# source.net
KiCad netlist of a schematic drawn in Altium Designer
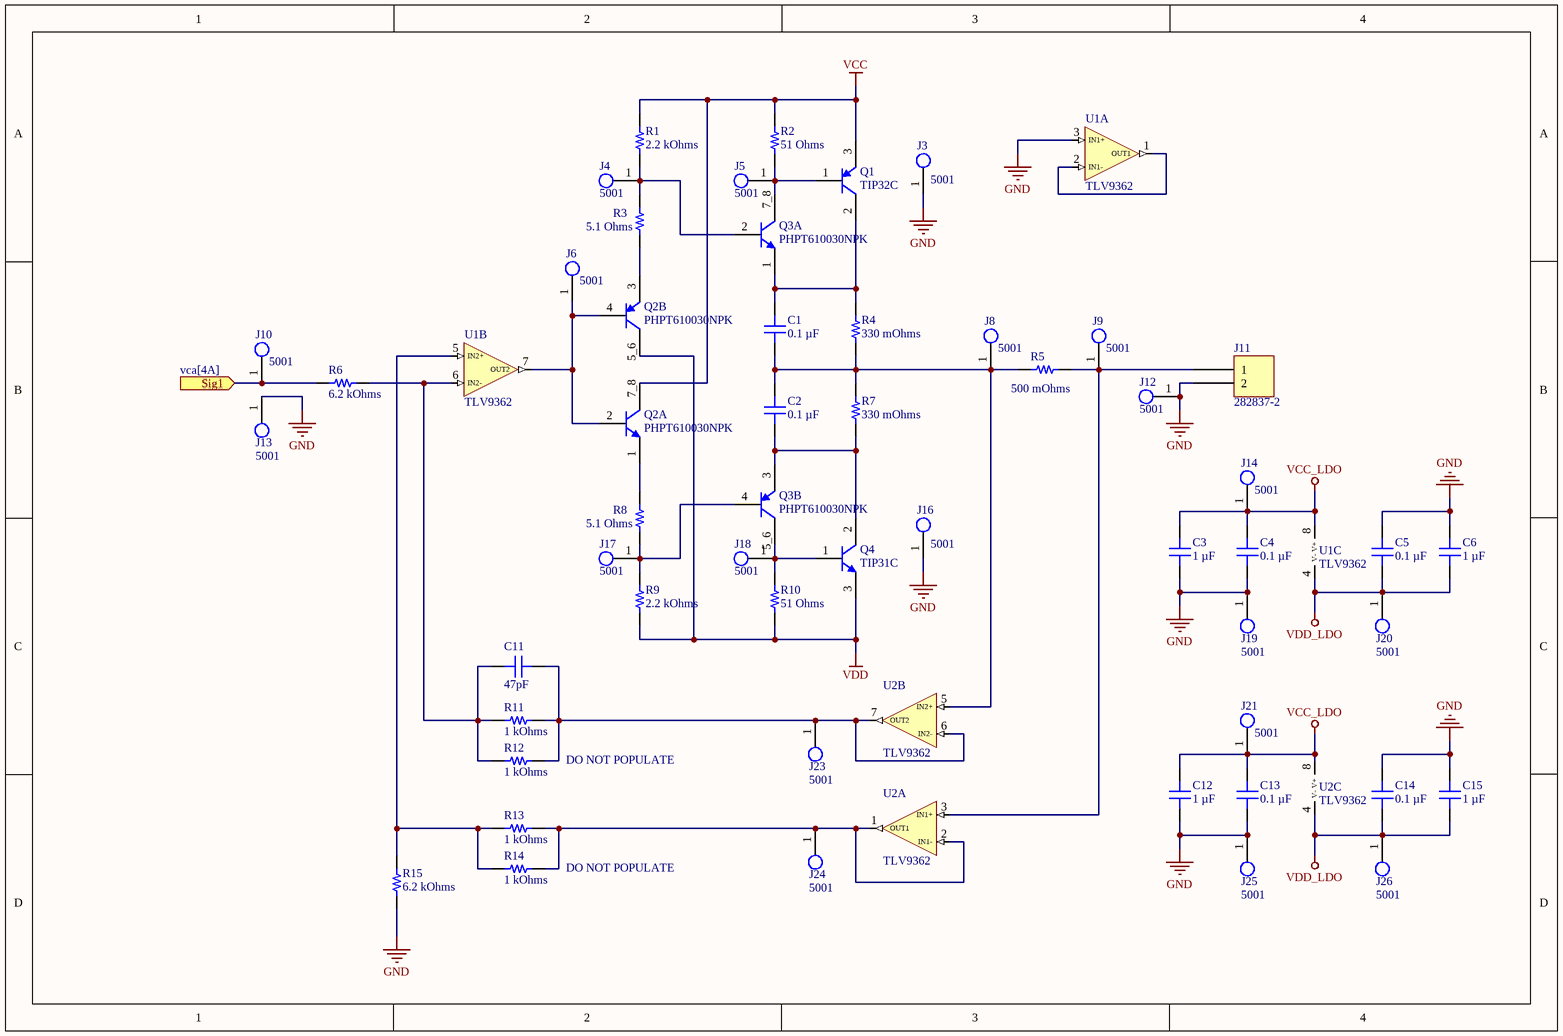
[diagram p0: source.SchDoc]

(export (version "E")
  (design (tool "Eeschema 10.0.6"))
  (components
    (comp (ref "C1")
      (value "0.1 µF")
      (footprint "CAP 1206_3216 - 0.8MM")
      (description "CAP CER 0.1UF 50V X7R 1206")
      (fields
        (field (name "PART NUMBER") "885012208087")
        (field (name "CAPACITANCE") "0.1 µF")
        (field (name "MANUFACTURER") "Würth Elektronik")
      )
      (libsource (lib "Celestial Altium Library - altium_library") (part "Capacitor"))
    )
    (comp (ref "C2")
      (value "0.1 µF")
      (footprint "CAP 1206_3216 - 0.8MM")
      (description "CAP CER 0.1UF 50V X7R 1206")
      (fields
        (field (name "PART NUMBER") "885012208087")
        (field (name "CAPACITANCE") "0.1 µF")
        (field (name "MANUFACTURER") "Würth Elektronik")
      )
      (libsource (lib "Celestial Altium Library - altium_library") (part "Capacitor"))
    )
    (comp (ref "C3")
      (value "1 µF")
      (footprint "CAP 1206_3216 - 0.8MM")
      (description "CAP CER 1UF 50V X7R 1206")
      (fields
        (field (name "PART NUMBER") "885012208093")
        (field (name "CAPACITANCE") "1 µF")
        (field (name "MANUFACTURER") "Würth Elektronik")
      )
      (libsource (lib "Celestial Altium Library - altium_library") (part "Capacitor"))
    )
    (comp (ref "C4")
      (value "0.1 µF")
      (footprint "CAP 1206_3216 - 0.8MM")
      (description "CAP CER 0.1UF 50V X7R 1206")
      (fields
        (field (name "PART NUMBER") "885012208087")
        (field (name "CAPACITANCE") "0.1 µF")
        (field (name "MANUFACTURER") "Würth Elektronik")
      )
      (libsource (lib "Celestial Altium Library - altium_library") (part "Capacitor"))
    )
    (comp (ref "C5")
      (value "0.1 µF")
      (footprint "CAP 1206_3216 - 0.8MM")
      (description "CAP CER 0.1UF 50V X7R 1206")
      (fields
        (field (name "PART NUMBER") "885012208087")
        (field (name "CAPACITANCE") "0.1 µF")
        (field (name "MANUFACTURER") "Würth Elektronik")
      )
      (libsource (lib "Celestial Altium Library - altium_library") (part "Capacitor"))
    )
    (comp (ref "C6")
      (value "1 µF")
      (footprint "CAP 1206_3216 - 0.8MM")
      (description "CAP CER 1UF 50V X7R 1206")
      (fields
        (field (name "PART NUMBER") "885012208093")
        (field (name "CAPACITANCE") "1 µF")
        (field (name "MANUFACTURER") "Würth Elektronik")
      )
      (libsource (lib "Celestial Altium Library - altium_library") (part "Capacitor"))
    )
    (comp (ref "C11")
      (value "47pF")
      (footprint "CAP 1206_3216 - 1.8MM")
      (description "CAP CER 47PF 1KV C0G/NP0 1206")
      (fields
        (field (name "PART NUMBER") "1206AA470KAT1A")
        (field (name "CAPACITANCE") "47pF")
        (field (name "MANUFACTURER") "AVX Corporation")
      )
      (libsource (lib "Celestial Altium Library - altium_library") (part "Capacitor"))
    )
    (comp (ref "C12")
      (value "1 µF")
      (footprint "CAP 1206_3216 - 0.8MM")
      (description "CAP CER 1UF 50V X7R 1206")
      (fields
        (field (name "PART NUMBER") "885012208093")
        (field (name "CAPACITANCE") "1 µF")
        (field (name "MANUFACTURER") "Würth Elektronik")
      )
      (libsource (lib "Celestial Altium Library - altium_library") (part "Capacitor"))
    )
    (comp (ref "C13")
      (value "0.1 µF")
      (footprint "CAP 1206_3216 - 0.8MM")
      (description "CAP CER 0.1UF 50V X7R 1206")
      (fields
        (field (name "PART NUMBER") "885012208087")
        (field (name "CAPACITANCE") "0.1 µF")
        (field (name "MANUFACTURER") "Würth Elektronik")
      )
      (libsource (lib "Celestial Altium Library - altium_library") (part "Capacitor"))
    )
    (comp (ref "C14")
      (value "0.1 µF")
      (footprint "CAP 1206_3216 - 0.8MM")
      (description "CAP CER 0.1UF 50V X7R 1206")
      (fields
        (field (name "PART NUMBER") "885012208087")
        (field (name "CAPACITANCE") "0.1 µF")
        (field (name "MANUFACTURER") "Würth Elektronik")
      )
      (libsource (lib "Celestial Altium Library - altium_library") (part "Capacitor"))
    )
    (comp (ref "C15")
      (value "1 µF")
      (footprint "CAP 1206_3216 - 0.8MM")
      (description "CAP CER 1UF 50V X7R 1206")
      (fields
        (field (name "PART NUMBER") "885012208093")
        (field (name "CAPACITANCE") "1 µF")
        (field (name "MANUFACTURER") "Würth Elektronik")
      )
      (libsource (lib "Celestial Altium Library - altium_library") (part "Capacitor"))
    )
    (comp (ref "J3")
      (value "5001")
      (footprint "FP-5001-MFG")
      (description "PC TEST POINT MINIATURE BLACK")
      (libsource (lib "za_koncar") (part "CMP-2000-05181-2"))
    )
    (comp (ref "J4")
      (value "5001")
      (footprint "FP-5001-MFG")
      (description "PC TEST POINT MINIATURE BLACK")
      (libsource (lib "za_koncar") (part "CMP-2000-05181-2"))
    )
    (comp (ref "J5")
      (value "5001")
      (footprint "FP-5001-MFG")
      (description "PC TEST POINT MINIATURE BLACK")
      (libsource (lib "za_koncar") (part "CMP-2000-05181-2"))
    )
    (comp (ref "J6")
      (value "5001")
      (footprint "FP-5001-MFG")
      (description "PC TEST POINT MINIATURE BLACK")
      (libsource (lib "za_koncar") (part "CMP-2000-05181-2"))
    )
    (comp (ref "J8")
      (value "5001")
      (footprint "FP-5001-MFG")
      (description "PC TEST POINT MINIATURE BLACK")
      (libsource (lib "za_koncar") (part "CMP-2000-05181-2"))
    )
    (comp (ref "J9")
      (value "5001")
      (footprint "FP-5001-MFG")
      (description "PC TEST POINT MINIATURE BLACK")
      (libsource (lib "za_koncar") (part "CMP-2000-05181-2"))
    )
    (comp (ref "J10")
      (value "5001")
      (footprint "FP-5001-MFG")
      (description "PC TEST POINT MINIATURE BLACK")
      (libsource (lib "za_koncar") (part "CMP-2000-05181-2"))
    )
    (comp (ref "J11")
      (value "282837-2")
      (footprint "TE 282837-2")
      (description "TERM BLK 2P SIDE ENT 5.08MM PCB")
      (fields (field (name "MANUFACTURER") "TE Connectivity AMP Connectors") (field (name "VOLTAGE") "300 V"))
      (libsource (lib "Celestial Altium Library - altium_library") (part "2 Pin"))
    )
    (comp (ref "J12")
      (value "5001")
      (footprint "FP-5001-MFG")
      (description "PC TEST POINT MINIATURE BLACK")
      (libsource (lib "za_koncar") (part "CMP-2000-05181-2"))
    )
    (comp (ref "J13")
      (value "5001")
      (footprint "FP-5001-MFG")
      (description "PC TEST POINT MINIATURE BLACK")
      (libsource (lib "za_koncar") (part "CMP-2000-05181-2"))
    )
    (comp (ref "J14")
      (value "5001")
      (footprint "FP-5001-MFG")
      (description "PC TEST POINT MINIATURE BLACK")
      (libsource (lib "za_koncar") (part "CMP-2000-05181-2"))
    )
    (comp (ref "J16")
      (value "5001")
      (footprint "FP-5001-MFG")
      (description "PC TEST POINT MINIATURE BLACK")
      (libsource (lib "za_koncar") (part "CMP-2000-05181-2"))
    )
    (comp (ref "J17")
      (value "5001")
      (footprint "FP-5001-MFG")
      (description "PC TEST POINT MINIATURE BLACK")
      (libsource (lib "za_koncar") (part "CMP-2000-05181-2"))
    )
    (comp (ref "J18")
      (value "5001")
      (footprint "FP-5001-MFG")
      (description "PC TEST POINT MINIATURE BLACK")
      (libsource (lib "za_koncar") (part "CMP-2000-05181-2"))
    )
    (comp (ref "J19")
      (value "5001")
      (footprint "FP-5001-MFG")
      (description "PC TEST POINT MINIATURE BLACK")
      (libsource (lib "za_koncar") (part "CMP-2000-05181-2"))
    )
    (comp (ref "J20")
      (value "5001")
      (footprint "FP-5001-MFG")
      (description "PC TEST POINT MINIATURE BLACK")
      (libsource (lib "za_koncar") (part "CMP-2000-05181-2"))
    )
    (comp (ref "J21")
      (value "5001")
      (footprint "FP-5001-MFG")
      (description "PC TEST POINT MINIATURE BLACK")
      (libsource (lib "za_koncar") (part "CMP-2000-05181-2"))
    )
    (comp (ref "J23")
      (value "5001")
      (footprint "FP-5001-MFG")
      (description "PC TEST POINT MINIATURE BLACK")
      (libsource (lib "za_koncar") (part "CMP-2000-05181-2"))
    )
    (comp (ref "J24")
      (value "5001")
      (footprint "FP-5001-MFG")
      (description "PC TEST POINT MINIATURE BLACK")
      (libsource (lib "za_koncar") (part "CMP-2000-05181-2"))
    )
    (comp (ref "J25")
      (value "5001")
      (footprint "FP-5001-MFG")
      (description "PC TEST POINT MINIATURE BLACK")
      (libsource (lib "za_koncar") (part "CMP-2000-05181-2"))
    )
    (comp (ref "J26")
      (value "5001")
      (footprint "FP-5001-MFG")
      (description "PC TEST POINT MINIATURE BLACK")
      (libsource (lib "za_koncar") (part "CMP-2000-05181-2"))
    )
    (comp (ref "Q1")
      (value "TIP32C")
      (footprint "ONSC-TO-220-3-221A-09")
      (description "Complementary Silicon Plastic Power Transistor, 3-Pin TO-220, Tube")
      (fields (field (name "MANUFACTURER") "On Semiconductor"))
      (libsource (lib "ON Semi General Purpose Transistors") (part "TIP32C"))
    )
    (comp (ref "Q2")
      (value "PHPT610030NPK")
      (footprint "TRANS_BUK9K18-40E,115")
      (libsource (lib "za_koncar") (part "PHPT610030NPK"))
    )
    (comp (ref "Q3")
      (value "PHPT610030NPK")
      (footprint "TRANS_BUK9K18-40E,115")
      (libsource (lib "za_koncar") (part "PHPT610030NPK"))
    )
    (comp (ref "Q4")
      (value "TIP31C")
      (footprint "ONSC-TO-220-3-221A-09")
      (description "Complementary Silicon Plastic Power Transistor, 3-Pin TO-220, Tube")
      (fields (field (name "MANUFACTURER") "On Semiconductor"))
      (libsource (lib "ON Semi General Purpose Transistors") (part "TIP31C"))
    )
    (comp (ref "R1")
      (value "2.2 kOhms")
      (footprint "RES 1206_3216")
      (description "RES SMD 2.2K OHM 5% 1/4W 1206")
      (fields
        (field (name "PART NUMBER") "ERJ-8GEYJ222V")
        (field (name "MANUFACTURER") "Panasonic Electronic Components")
      )
      (libsource (lib "Celestial Altium Library - altium_library") (part "Resistor"))
    )
    (comp (ref "R2")
      (value "51 Ohms")
      (footprint "RES 1206_3216")
      (description "RES SMD 51 OHM 5% 1/4W 1206")
      (fields
        (field (name "PART NUMBER") "ERJ-8GEYJ510V")
        (field (name "MANUFACTURER") "Panasonic Electronic Components")
      )
      (libsource (lib "Celestial Altium Library - altium_library") (part "Resistor"))
    )
    (comp (ref "R3")
      (value "5.1 Ohms")
      (footprint "RES 1206_3216")
      (description "RES SMD 5.1 OHM 5% 1/4W 1206")
      (fields
        (field (name "PART NUMBER") "ERJ-8GEYJ5R1V")
        (field (name "MANUFACTURER") "Panasonic Electronic Components")
      )
      (libsource (lib "Celestial Altium Library - altium_library") (part "Resistor"))
    )
    (comp (ref "R4")
      (value "330 mOhms")
      (footprint "STACKPOLE CSR2512")
      (description "RES 0.33 OHM 1% 2W 2512")
      (fields
        (field (name "PART NUMBER") "CSRN2512FKR330")
        (field (name "MANUFACTURER") "Stackpole Electronics Inc")
      )
      (libsource (lib "Celestial Altium Library - altium_library") (part "Resistor"))
    )
    (comp (ref "R5")
      (value "500 mOhms")
      (footprint "STACKPOLE CSR2512")
      (description "RES 0.5 OHM 1% 2W 2512")
      (fields
        (field (name "PART NUMBER") "CSRN2512FKR500")
        (field (name "MANUFACTURER") "Stackpole Electronics Inc")
      )
      (libsource (lib "Celestial Altium Library - altium_library") (part "Resistor"))
    )
    (comp (ref "R6")
      (value "6.2 kOhms")
      (footprint "RES 1206_3216")
      (description "RES SMD 6.2K OHM 0.1% 1/4W 1206")
      (fields
        (field (name "PART NUMBER") "ERA-8AEB622V")
        (field (name "MANUFACTURER") "Panasonic Electronic Components")
      )
      (libsource (lib "Celestial Altium Library - altium_library") (part "Resistor"))
    )
    (comp (ref "R7")
      (value "330 mOhms")
      (footprint "STACKPOLE CSR2512")
      (description "RES 0.33 OHM 1% 2W 2512")
      (fields
        (field (name "PART NUMBER") "CSRN2512FKR330")
        (field (name "MANUFACTURER") "Stackpole Electronics Inc")
      )
      (libsource (lib "Celestial Altium Library - altium_library") (part "Resistor"))
    )
    (comp (ref "R8")
      (value "5.1 Ohms")
      (footprint "RES 1206_3216")
      (description "RES SMD 5.1 OHM 5% 1/4W 1206")
      (fields
        (field (name "PART NUMBER") "ERJ-8GEYJ5R1V")
        (field (name "MANUFACTURER") "Panasonic Electronic Components")
      )
      (libsource (lib "Celestial Altium Library - altium_library") (part "Resistor"))
    )
    (comp (ref "R9")
      (value "2.2 kOhms")
      (footprint "RES 1206_3216")
      (description "RES SMD 2.2K OHM 5% 1/4W 1206")
      (fields
        (field (name "PART NUMBER") "ERJ-8GEYJ222V")
        (field (name "MANUFACTURER") "Panasonic Electronic Components")
      )
      (libsource (lib "Celestial Altium Library - altium_library") (part "Resistor"))
    )
    (comp (ref "R10")
      (value "51 Ohms")
      (footprint "RES 1206_3216")
      (description "RES SMD 51 OHM 5% 1/4W 1206")
      (fields
        (field (name "PART NUMBER") "ERJ-8GEYJ510V")
        (field (name "MANUFACTURER") "Panasonic Electronic Components")
      )
      (libsource (lib "Celestial Altium Library - altium_library") (part "Resistor"))
    )
    (comp (ref "R11")
      (value "1 kOhms")
      (footprint "RES 1206_3216")
      (description "RES SMD 1K OHM 0.1% 1/4W 1206")
      (fields
        (field (name "PART NUMBER") "ERA-8AEB102V")
        (field (name "MANUFACTURER") "Panasonic Electronic Components")
      )
      (libsource (lib "Celestial Altium Library - altium_library") (part "Resistor"))
    )
    (comp (ref "R12")
      (value "1 kOhms")
      (footprint "RES 1206_3216")
      (description "RES SMD 1K OHM 0.1% 1/4W 1206")
      (fields
        (field (name "PART NUMBER") "ERA-8AEB102V")
        (field (name "MANUFACTURER") "Panasonic Electronic Components")
      )
      (libsource (lib "Celestial Altium Library - altium_library") (part "Resistor"))
    )
    (comp (ref "R13")
      (value "1 kOhms")
      (footprint "RES 1206_3216")
      (description "RES SMD 1K OHM 0.1% 1/4W 1206")
      (fields
        (field (name "PART NUMBER") "ERA-8AEB102V")
        (field (name "MANUFACTURER") "Panasonic Electronic Components")
      )
      (libsource (lib "Celestial Altium Library - altium_library") (part "Resistor"))
    )
    (comp (ref "R14")
      (value "1 kOhms")
      (footprint "RES 1206_3216")
      (description "RES SMD 1K OHM 0.1% 1/4W 1206")
      (fields
        (field (name "PART NUMBER") "ERA-8AEB102V")
        (field (name "MANUFACTURER") "Panasonic Electronic Components")
      )
      (libsource (lib "Celestial Altium Library - altium_library") (part "Resistor"))
    )
    (comp (ref "R15")
      (value "6.2 kOhms")
      (footprint "RES 1206_3216")
      (description "RES SMD 6.2K OHM 0.1% 1/4W 1206")
      (fields
        (field (name "PART NUMBER") "ERA-8AEB622V")
        (field (name "MANUFACTURER") "Panasonic Electronic Components")
      )
      (libsource (lib "Celestial Altium Library - altium_library") (part "Resistor"))
    )
    (comp (ref "U1")
      (value "TLV9362")
      (footprint "za_koncar:SOIC8-127P600X175-8N")
      (description "TLV936x 10-MHz, 40-V, RRO, Operational Amplifie")
      (libsource (lib "za_koncar") (part "TLV9362"))
    )
    (comp (ref "U2")
      (value "TLV9362")
      (footprint "za_koncar:SOIC8-127P600X175-8N")
      (description "TLV936x 10-MHz, 40-V, RRO, Operational Amplifie")
      (libsource (lib "za_koncar") (part "TLV9362"))
    )
  )
  (nets
    (net (code "1") (name "/Sig1") (class "Default")
      (node (ref "J10") (pin "1") (pinfunction "1_1") (pintype "passive"))
      (node (ref "R6") (pin "2") (pinfunction "2_2") (pintype "passive"))
    )
    (net (code "2") (name "GND") (class "Default")
      (node (ref "C12") (pin "1") (pinfunction "1_1") (pintype "passive"))
      (node (ref "C13") (pin "1") (pinfunction "1_1") (pintype "passive"))
      (node (ref "C14") (pin "2") (pinfunction "2_2") (pintype "passive"))
      (node (ref "C15") (pin "2") (pinfunction "2_2") (pintype "passive"))
      (node (ref "C3") (pin "1") (pinfunction "1_1") (pintype "passive"))
      (node (ref "C4") (pin "1") (pinfunction "1_1") (pintype "passive"))
      (node (ref "C5") (pin "2") (pinfunction "2_2") (pintype "passive"))
      (node (ref "C6") (pin "2") (pinfunction "2_2") (pintype "passive"))
      (node (ref "J11") (pin "2") (pinfunction "2_2") (pintype "passive"))
      (node (ref "J12") (pin "1") (pinfunction "1_1") (pintype "passive"))
      (node (ref "J13") (pin "1") (pinfunction "1_1") (pintype "passive"))
      (node (ref "J16") (pin "1") (pinfunction "1_1") (pintype "passive"))
      (node (ref "J19") (pin "1") (pinfunction "1_1") (pintype "passive"))
      (node (ref "J25") (pin "1") (pinfunction "1_1") (pintype "passive"))
      (node (ref "J3") (pin "1") (pinfunction "1_1") (pintype "passive"))
      (node (ref "R15") (pin "1") (pinfunction "1_1") (pintype "passive"))
      (node (ref "U1") (pin "3") (pinfunction "IN1+_3") (pintype "input"))
    )
    (net (code "3") (name "Net-(Q1-B)") (class "Default")
      (node (ref "J5") (pin "1") (pinfunction "1_1") (pintype "passive"))
      (node (ref "Q1") (pin "1") (pinfunction "B_1") (pintype "passive"))
      (node (ref "Q3") (pin "7_8") (pinfunction "C1_7_8") (pintype "passive"))
      (node (ref "R2") (pin "1") (pinfunction "1_1") (pintype "passive"))
    )
    (net (code "4") (name "Net-(Q1-C)") (class "Default")
      (node (ref "C1") (pin "2") (pinfunction "2_2") (pintype "passive"))
      (node (ref "Q1") (pin "2") (pinfunction "C_2") (pintype "passive"))
      (node (ref "Q3") (pin "1") (pinfunction "E1_1") (pintype "passive"))
      (node (ref "R4") (pin "2") (pinfunction "2_2") (pintype "passive"))
    )
    (net (code "5") (name "Net-(Q2A-B1)") (class "Default")
      (node (ref "J6") (pin "1") (pinfunction "1_1") (pintype "passive"))
      (node (ref "Q2") (pin "2") (pinfunction "B1_2") (pintype "passive"))
      (node (ref "Q2") (pin "4") (pinfunction "B2_4") (pintype "passive"))
      (node (ref "U1") (pin "7") (pinfunction "OUT2_7") (pintype "output"))
    )
    (net (code "6") (name "Net-(Q2A-E1)") (class "Default")
      (node (ref "Q2") (pin "1") (pinfunction "E1_1") (pintype "passive"))
      (node (ref "R8") (pin "2") (pinfunction "2_2") (pintype "passive"))
    )
    (net (code "7") (name "Net-(Q2B-E2)") (class "Default")
      (node (ref "Q2") (pin "3") (pinfunction "E2_3") (pintype "passive"))
      (node (ref "R3") (pin "1") (pinfunction "1_1") (pintype "passive"))
    )
    (net (code "8") (name "Net-(Q3A-B1)") (class "Default")
      (node (ref "J4") (pin "1") (pinfunction "1_1") (pintype "passive"))
      (node (ref "Q3") (pin "2") (pinfunction "B1_2") (pintype "passive"))
      (node (ref "R1") (pin "1") (pinfunction "1_1") (pintype "passive"))
      (node (ref "R3") (pin "2") (pinfunction "2_2") (pintype "passive"))
    )
    (net (code "9") (name "Net-(Q3B-B2)") (class "Default")
      (node (ref "J17") (pin "1") (pinfunction "1_1") (pintype "passive"))
      (node (ref "Q3") (pin "4") (pinfunction "B2_4") (pintype "passive"))
      (node (ref "R8") (pin "1") (pinfunction "1_1") (pintype "passive"))
      (node (ref "R9") (pin "2") (pinfunction "2_2") (pintype "passive"))
    )
    (net (code "10") (name "Net-(Q3B-C2)") (class "Default")
      (node (ref "J18") (pin "1") (pinfunction "1_1") (pintype "passive"))
      (node (ref "Q3") (pin "5_6") (pinfunction "C2_5_6") (pintype "passive"))
      (node (ref "Q4") (pin "1") (pinfunction "B_1") (pintype "passive"))
      (node (ref "R10") (pin "2") (pinfunction "2_2") (pintype "passive"))
    )
    (net (code "11") (name "Net-(Q3B-E2)") (class "Default")
      (node (ref "C2") (pin "1") (pinfunction "1_1") (pintype "passive"))
      (node (ref "Q3") (pin "3") (pinfunction "E2_3") (pintype "passive"))
      (node (ref "Q4") (pin "2") (pinfunction "C_2") (pintype "passive"))
      (node (ref "R7") (pin "1") (pinfunction "1_1") (pintype "passive"))
    )
    (net (code "12") (name "Net-(U1A-IN1-)") (class "Default")
      (node (ref "U1") (pin "1") (pinfunction "OUT1_1") (pintype "output"))
      (node (ref "U1") (pin "2") (pinfunction "IN1-_2") (pintype "input"))
    )
    (net (code "13") (name "Net-(U1B-IN2+)") (class "Default")
      (node (ref "R13") (pin "1") (pinfunction "1_1") (pintype "passive"))
      (node (ref "R14") (pin "1") (pinfunction "1_1") (pintype "passive"))
      (node (ref "R15") (pin "2") (pinfunction "2_2") (pintype "passive"))
      (node (ref "U1") (pin "5") (pinfunction "IN2+_5") (pintype "input"))
    )
    (net (code "14") (name "Net-(U1B-IN2-)") (class "Default")
      (node (ref "C11") (pin "1") (pinfunction "1_1") (pintype "passive"))
      (node (ref "R11") (pin "1") (pinfunction "1_1") (pintype "passive"))
      (node (ref "R12") (pin "1") (pinfunction "1_1") (pintype "passive"))
      (node (ref "R6") (pin "1") (pinfunction "1_1") (pintype "passive"))
      (node (ref "U1") (pin "6") (pinfunction "IN2-_6") (pintype "input"))
    )
    (net (code "15") (name "Net-(U2A-IN1+)") (class "Default")
      (node (ref "J11") (pin "1") (pinfunction "1_1") (pintype "passive"))
      (node (ref "J9") (pin "1") (pinfunction "1_1") (pintype "passive"))
      (node (ref "R5") (pin "1") (pinfunction "1_1") (pintype "passive"))
      (node (ref "U2") (pin "3") (pinfunction "IN1+_3") (pintype "input"))
    )
    (net (code "16") (name "Net-(U2A-IN1-)") (class "Default")
      (node (ref "J24") (pin "1") (pinfunction "1_1") (pintype "passive"))
      (node (ref "R13") (pin "2") (pinfunction "2_2") (pintype "passive"))
      (node (ref "R14") (pin "2") (pinfunction "2_2") (pintype "passive"))
      (node (ref "U2") (pin "1") (pinfunction "OUT1_1") (pintype "output"))
      (node (ref "U2") (pin "2") (pinfunction "IN1-_2") (pintype "input"))
    )
    (net (code "17") (name "Net-(U2B-IN2+)") (class "Default")
      (node (ref "C1") (pin "1") (pinfunction "1_1") (pintype "passive"))
      (node (ref "C2") (pin "2") (pinfunction "2_2") (pintype "passive"))
      (node (ref "J8") (pin "1") (pinfunction "1_1") (pintype "passive"))
      (node (ref "R4") (pin "1") (pinfunction "1_1") (pintype "passive"))
      (node (ref "R5") (pin "2") (pinfunction "2_2") (pintype "passive"))
      (node (ref "R7") (pin "2") (pinfunction "2_2") (pintype "passive"))
      (node (ref "U2") (pin "5") (pinfunction "IN2+_5") (pintype "input"))
    )
    (net (code "18") (name "Net-(U2B-IN2-)") (class "Default")
      (node (ref "C11") (pin "2") (pinfunction "2_2") (pintype "passive"))
      (node (ref "J23") (pin "1") (pinfunction "1_1") (pintype "passive"))
      (node (ref "R11") (pin "2") (pinfunction "2_2") (pintype "passive"))
      (node (ref "R12") (pin "2") (pinfunction "2_2") (pintype "passive"))
      (node (ref "U2") (pin "6") (pinfunction "IN2-_6") (pintype "input"))
      (node (ref "U2") (pin "7") (pinfunction "OUT2_7") (pintype "output"))
    )
    (net (code "19") (name "VCC") (class "Default")
      (node (ref "Q1") (pin "3") (pinfunction "E_3") (pintype "passive"))
      (node (ref "Q2") (pin "7_8") (pinfunction "C1_7_8") (pintype "passive"))
      (node (ref "R1") (pin "2") (pinfunction "2_2") (pintype "passive"))
      (node (ref "R2") (pin "2") (pinfunction "2_2") (pintype "passive"))
    )
    (net (code "20") (name "VCC_LDO") (class "Default")
      (node (ref "C12") (pin "2") (pinfunction "2_2") (pintype "passive"))
      (node (ref "C13") (pin "2") (pinfunction "2_2") (pintype "passive"))
      (node (ref "C3") (pin "2") (pinfunction "2_2") (pintype "passive"))
      (node (ref "C4") (pin "2") (pinfunction "2_2") (pintype "passive"))
      (node (ref "J14") (pin "1") (pinfunction "1_1") (pintype "passive"))
      (node (ref "J21") (pin "1") (pinfunction "1_1") (pintype "passive"))
      (node (ref "U1") (pin "8") (pinfunction "V+_8") (pintype "power_in"))
      (node (ref "U2") (pin "8") (pinfunction "V+_8") (pintype "power_in"))
    )
    (net (code "21") (name "VDD") (class "Default")
      (node (ref "Q2") (pin "5_6") (pinfunction "C2_5_6") (pintype "passive"))
      (node (ref "Q4") (pin "3") (pinfunction "E_3") (pintype "passive"))
      (node (ref "R10") (pin "1") (pinfunction "1_1") (pintype "passive"))
      (node (ref "R9") (pin "1") (pinfunction "1_1") (pintype "passive"))
    )
    (net (code "22") (name "VDD_LDO") (class "Default")
      (node (ref "C14") (pin "1") (pinfunction "1_1") (pintype "passive"))
      (node (ref "C15") (pin "1") (pinfunction "1_1") (pintype "passive"))
      (node (ref "C5") (pin "1") (pinfunction "1_1") (pintype "passive"))
      (node (ref "C6") (pin "1") (pinfunction "1_1") (pintype "passive"))
      (node (ref "J20") (pin "1") (pinfunction "1_1") (pintype "passive"))
      (node (ref "J26") (pin "1") (pinfunction "1_1") (pintype "passive"))
      (node (ref "U1") (pin "4") (pinfunction "V-_4") (pintype "power_in"))
      (node (ref "U2") (pin "4") (pinfunction "V-_4") (pintype "power_in"))
    )
  )
)
